# usbDac.net
KiCad netlist of a schematic drawn in EAGLE
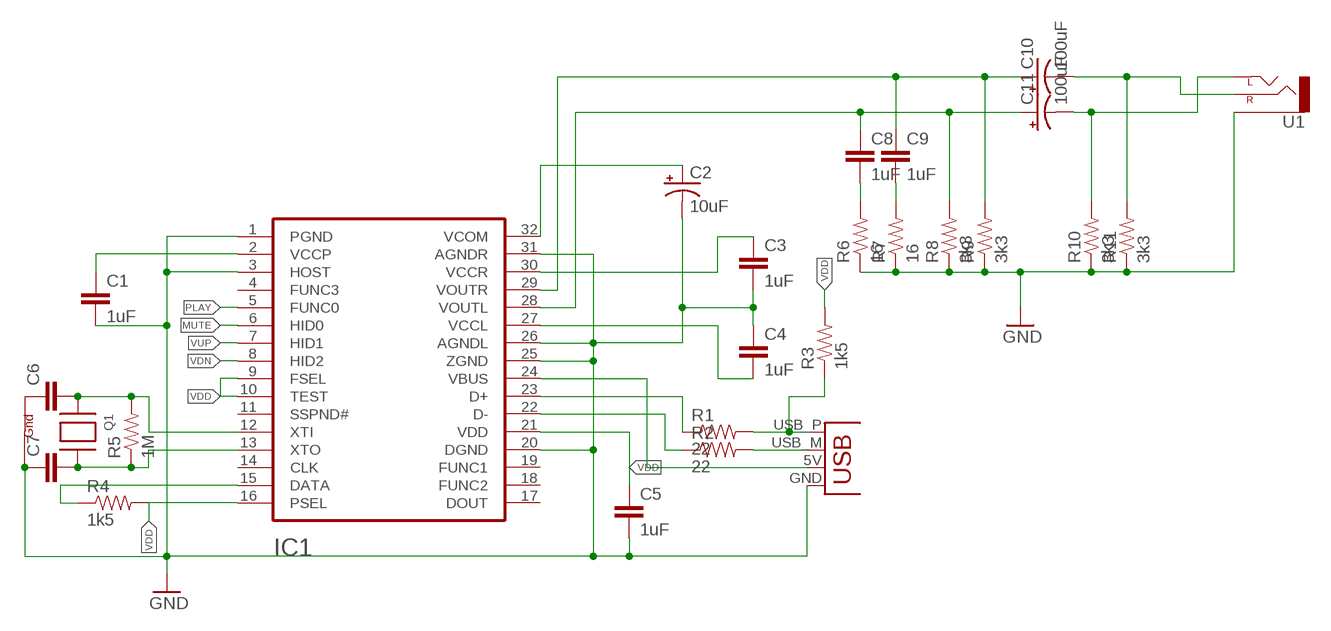
[diagram p0: schematic, sheet 1]

(export (version "E")
  (design (tool "Eeschema 10.0.6"))
  (components
    (comp (ref "C1")
      (value "1uF")
      (footprint "eagle-import:0603-CAP")
      (libsource (lib "eagle-import") (part "CAP0603-CAP"))
    )
    (comp (ref "C2")
      (value "10uF")
      (footprint "eagle-import:EIA3216")
      (libsource (lib "eagle-import") (part "CAP_POL1206"))
    )
    (comp (ref "C3")
      (value "1uF")
      (footprint "eagle-import:0603-CAP")
      (libsource (lib "eagle-import") (part "CAP0603-CAP"))
    )
    (comp (ref "C4")
      (value "1uF")
      (footprint "eagle-import:0603-CAP")
      (libsource (lib "eagle-import") (part "CAP0603-CAP"))
    )
    (comp (ref "C5")
      (value "1uF")
      (footprint "eagle-import:0603-CAP")
      (libsource (lib "eagle-import") (part "CAP0603-CAP"))
    )
    (comp (ref "C6")
      (value "CAP0603-CAP")
      (footprint "eagle-import:0603-CAP")
      (libsource (lib "eagle-import") (part "CAP0603-CAP"))
    )
    (comp (ref "C7")
      (value "CAP0603-CAP")
      (footprint "eagle-import:0603-CAP")
      (libsource (lib "eagle-import") (part "CAP0603-CAP"))
    )
    (comp (ref "C8")
      (value "1uF")
      (footprint "eagle-import:0603-CAP")
      (libsource (lib "eagle-import") (part "CAP0603-CAP"))
    )
    (comp (ref "C9")
      (value "1uF")
      (footprint "eagle-import:0603-CAP")
      (libsource (lib "eagle-import") (part "CAP0603-CAP"))
    )
    (comp (ref "C10")
      (value "100uF")
      (footprint "eagle-import:PANASONIC_C")
      (libsource (lib "eagle-import") (part "CAP_POLC"))
    )
    (comp (ref "C11")
      (value "100uF")
      (footprint "eagle-import:PANASONIC_C")
      (libsource (lib "eagle-import") (part "CAP_POLC"))
    )
    (comp (ref "IC1")
      (value "PCM2706")
      (footprint "eagle-import:TQFP32")
      (libsource (lib "eagle-import") (part "PCM2706"))
    )
    (comp (ref "Q1")
      (value "XTAL-4-3225")
      (footprint "eagle-import:NX3225")
      (libsource (lib "eagle-import") (part "XTAL-4-3225"))
    )
    (comp (ref "R1")
      (value "22")
      (footprint "eagle-import:0603-RES")
      (libsource (lib "eagle-import") (part "RESISTOR0603-RES"))
    )
    (comp (ref "R2")
      (value "22")
      (footprint "eagle-import:0603-RES")
      (libsource (lib "eagle-import") (part "RESISTOR0603-RES"))
    )
    (comp (ref "R3")
      (value "1k5")
      (footprint "eagle-import:0603-RES")
      (libsource (lib "eagle-import") (part "RESISTOR0603-RES"))
    )
    (comp (ref "R4")
      (value "1k5")
      (footprint "eagle-import:0603-RES")
      (libsource (lib "eagle-import") (part "RESISTOR0603-RES"))
    )
    (comp (ref "R5")
      (value "1M")
      (footprint "eagle-import:0603-RES")
      (libsource (lib "eagle-import") (part "RESISTOR0603-RES"))
    )
    (comp (ref "R6")
      (value "16")
      (footprint "eagle-import:0603-RES")
      (libsource (lib "eagle-import") (part "RESISTOR0603-RES"))
    )
    (comp (ref "R7")
      (value "16")
      (footprint "eagle-import:0603-RES")
      (libsource (lib "eagle-import") (part "RESISTOR0603-RES"))
    )
    (comp (ref "R8")
      (value "3k3")
      (footprint "eagle-import:0603-RES")
      (libsource (lib "eagle-import") (part "RESISTOR0603-RES"))
    )
    (comp (ref "R9")
      (value "3k3")
      (footprint "eagle-import:0603-RES")
      (libsource (lib "eagle-import") (part "RESISTOR0603-RES"))
    )
    (comp (ref "R10")
      (value "3k3")
      (footprint "eagle-import:0603-RES")
      (libsource (lib "eagle-import") (part "RESISTOR0603-RES"))
    )
    (comp (ref "R11")
      (value "3k3")
      (footprint "eagle-import:0603-RES")
      (libsource (lib "eagle-import") (part "RESISTOR0603-RES"))
    )
    (comp (ref "U1")
      (value "AUDIO-JACKSMD2")
      (footprint "eagle-import:AUDIO-JACK-3.5MM-SMD")
      (libsource (lib "eagle-import") (part "AUDIO-JACKSMD2"))
    )
    (comp (ref "X1")
      (value "USBPCB")
      (footprint "eagle-import:USB-A-PCB")
      (libsource (lib "eagle-import") (part "USBPCB"))
    )
  )
  (nets
    (net (code "1") (name "GND") (class "Default")
      (node (ref "C1") (pin "2") (pinfunction "2_2") (pintype "passive"))
      (node (ref "C2") (pin "C") (pinfunction "-_C") (pintype "passive"))
      (node (ref "C3") (pin "2") (pinfunction "2_2") (pintype "passive"))
      (node (ref "C4") (pin "1") (pinfunction "1_1") (pintype "passive"))
      (node (ref "C5") (pin "2") (pinfunction "2_2") (pintype "passive"))
      (node (ref "C7") (pin "1") (pinfunction "1_1") (pintype "passive"))
      (node (ref "IC1") (pin "1") (pinfunction "PGND_1") (pintype "bidirectional"))
      (node (ref "IC1") (pin "20") (pinfunction "DGND_20") (pintype "bidirectional"))
      (node (ref "IC1") (pin "25") (pinfunction "ZGND_25") (pintype "bidirectional"))
      (node (ref "IC1") (pin "26") (pinfunction "AGNDL_26") (pintype "bidirectional"))
      (node (ref "IC1") (pin "3") (pinfunction "HOST_3") (pintype "bidirectional"))
      (node (ref "IC1") (pin "31") (pinfunction "AGNDR_31") (pintype "bidirectional"))
      (node (ref "Q1") (pin "2") (pinfunction "G2_2") (pintype "power_in"))
      (node (ref "R10") (pin "1") (pinfunction "1_1") (pintype "passive"))
      (node (ref "R11") (pin "1") (pinfunction "1_1") (pintype "passive"))
      (node (ref "R6") (pin "1") (pinfunction "1_1") (pintype "passive"))
      (node (ref "R7") (pin "1") (pinfunction "1_1") (pintype "passive"))
      (node (ref "R8") (pin "1") (pinfunction "1_1") (pintype "passive"))
      (node (ref "R9") (pin "1") (pinfunction "1_1") (pintype "passive"))
      (node (ref "U1") (pin "SLEEVE") (pinfunction "SLEEVE_SLEEVE") (pintype "bidirectional"))
      (node (ref "X1") (pin "GND") (pinfunction "GND_GND") (pintype "bidirectional"))
    )
    (net (code "2") (name "MUTE") (class "Default")
      (node (ref "IC1") (pin "6") (pinfunction "HID0_6") (pintype "bidirectional"))
    )
    (net (code "3") (name "Net-(C2-+)") (class "Default")
      (node (ref "C2") (pin "A") (pinfunction "+_A") (pintype "passive"))
      (node (ref "IC1") (pin "32") (pinfunction "VCOM_32") (pintype "bidirectional"))
    )
    (net (code "4") (name "Net-(C8-Pad2)") (class "Default")
      (node (ref "C8") (pin "2") (pinfunction "2_2") (pintype "passive"))
      (node (ref "R6") (pin "2") (pinfunction "2_2") (pintype "passive"))
    )
    (net (code "5") (name "Net-(C9-Pad2)") (class "Default")
      (node (ref "C9") (pin "2") (pinfunction "2_2") (pintype "passive"))
      (node (ref "R7") (pin "2") (pinfunction "2_2") (pintype "passive"))
    )
    (net (code "6") (name "Net-(IC1-D+)") (class "Default")
      (node (ref "IC1") (pin "23") (pinfunction "D+_23") (pintype "bidirectional"))
      (node (ref "R1") (pin "1") (pinfunction "1_1") (pintype "passive"))
    )
    (net (code "7") (name "Net-(IC1-D-)") (class "Default")
      (node (ref "IC1") (pin "22") (pinfunction "D-_22") (pintype "bidirectional"))
      (node (ref "R2") (pin "1") (pinfunction "1_1") (pintype "passive"))
    )
    (net (code "8") (name "Net-(IC1-DATA)") (class "Default")
      (node (ref "IC1") (pin "15") (pinfunction "DATA_15") (pintype "bidirectional"))
      (node (ref "R4") (pin "1") (pinfunction "1_1") (pintype "passive"))
    )
    (net (code "9") (name "Net-(IC1-VBUS)") (class "Default")
      (node (ref "IC1") (pin "24") (pinfunction "VBUS_24") (pintype "bidirectional"))
      (node (ref "X1") (pin "5V") (pinfunction "VBUS_5V") (pintype "bidirectional"))
    )
    (net (code "10") (name "Net-(IC1-VCCL)") (class "Default")
      (node (ref "C4") (pin "2") (pinfunction "2_2") (pintype "passive"))
      (node (ref "IC1") (pin "27") (pinfunction "VCCL_27") (pintype "bidirectional"))
    )
    (net (code "11") (name "Net-(IC1-VCCP)") (class "Default")
      (node (ref "C1") (pin "1") (pinfunction "1_1") (pintype "passive"))
      (node (ref "IC1") (pin "2") (pinfunction "VCCP_2") (pintype "bidirectional"))
    )
    (net (code "12") (name "Net-(IC1-VCCR)") (class "Default")
      (node (ref "C3") (pin "1") (pinfunction "1_1") (pintype "passive"))
      (node (ref "IC1") (pin "30") (pinfunction "VCCR_30") (pintype "bidirectional"))
    )
    (net (code "13") (name "Net-(IC1-VOUTL)") (class "Default")
      (node (ref "C11") (pin "+") (pinfunction "+_+") (pintype "passive"))
      (node (ref "C8") (pin "1") (pinfunction "1_1") (pintype "passive"))
      (node (ref "IC1") (pin "28") (pinfunction "VOUTL_28") (pintype "bidirectional"))
      (node (ref "R8") (pin "2") (pinfunction "2_2") (pintype "passive"))
    )
    (net (code "14") (name "Net-(IC1-VOUTR)") (class "Default")
      (node (ref "C10") (pin "+") (pinfunction "+_+") (pintype "passive"))
      (node (ref "C9") (pin "1") (pinfunction "1_1") (pintype "passive"))
      (node (ref "IC1") (pin "29") (pinfunction "VOUTR_29") (pintype "bidirectional"))
      (node (ref "R9") (pin "2") (pinfunction "2_2") (pintype "passive"))
    )
    (net (code "15") (name "Net-(IC1-XTI)") (class "Default")
      (node (ref "C6") (pin "2") (pinfunction "2_2") (pintype "passive"))
      (node (ref "IC1") (pin "12") (pinfunction "XTI_12") (pintype "bidirectional"))
      (node (ref "Q1") (pin "1") (pinfunction "X1_1") (pintype "bidirectional"))
      (node (ref "R5") (pin "2") (pinfunction "2_2") (pintype "passive"))
    )
    (net (code "16") (name "Net-(IC1-XTO)") (class "Default")
      (node (ref "C7") (pin "2") (pinfunction "2_2") (pintype "passive"))
      (node (ref "IC1") (pin "13") (pinfunction "XTO_13") (pintype "bidirectional"))
      (node (ref "Q1") (pin "3") (pinfunction "X2_3") (pintype "bidirectional"))
      (node (ref "R5") (pin "1") (pinfunction "1_1") (pintype "passive"))
    )
    (net (code "17") (name "Net-(Q1-G1)") (class "Default")
      (node (ref "C6") (pin "1") (pinfunction "1_1") (pintype "passive"))
      (node (ref "Q1") (pin "4") (pinfunction "G1_4") (pintype "power_in"))
    )
    (net (code "18") (name "Net-(U1-LEFT)") (class "Default")
      (node (ref "C11") (pin "-") (pinfunction "-_-") (pintype "passive"))
      (node (ref "R10") (pin "2") (pinfunction "2_2") (pintype "passive"))
      (node (ref "U1") (pin "TIP") (pinfunction "LEFT_TIP") (pintype "bidirectional"))
    )
    (net (code "19") (name "Net-(U1-RIGHT)") (class "Default")
      (node (ref "C10") (pin "-") (pinfunction "-_-") (pintype "passive"))
      (node (ref "R11") (pin "2") (pinfunction "2_2") (pintype "passive"))
      (node (ref "U1") (pin "RING") (pinfunction "RIGHT_RING") (pintype "bidirectional"))
    )
    (net (code "20") (name "Net-(X1-D+)") (class "Default")
      (node (ref "R1") (pin "2") (pinfunction "2_2") (pintype "passive"))
      (node (ref "R3") (pin "1") (pinfunction "1_1") (pintype "passive"))
      (node (ref "X1") (pin "USB_P") (pinfunction "D+_USB_P") (pintype "bidirectional"))
    )
    (net (code "21") (name "Net-(X1-D-)") (class "Default")
      (node (ref "R2") (pin "2") (pinfunction "2_2") (pintype "passive"))
      (node (ref "X1") (pin "USB_M") (pinfunction "D-_USB_M") (pintype "bidirectional"))
    )
    (net (code "22") (name "PLAY") (class "Default")
      (node (ref "IC1") (pin "5") (pinfunction "FUNC0_5") (pintype "bidirectional"))
    )
    (net (code "23") (name "VDD") (class "Default")
      (node (ref "C5") (pin "1") (pinfunction "1_1") (pintype "passive"))
      (node (ref "IC1") (pin "10") (pinfunction "TEST_10") (pintype "bidirectional"))
      (node (ref "IC1") (pin "16") (pinfunction "PSEL_16") (pintype "bidirectional"))
      (node (ref "IC1") (pin "21") (pinfunction "VDD_21") (pintype "bidirectional"))
      (node (ref "IC1") (pin "9") (pinfunction "FSEL_9") (pintype "bidirectional"))
      (node (ref "R3") (pin "2") (pinfunction "2_2") (pintype "passive"))
      (node (ref "R4") (pin "2") (pinfunction "2_2") (pintype "passive"))
    )
    (net (code "24") (name "VDN") (class "Default")
      (node (ref "IC1") (pin "8") (pinfunction "HID2_8") (pintype "bidirectional"))
    )
    (net (code "25") (name "VUP") (class "Default")
      (node (ref "IC1") (pin "7") (pinfunction "HID1_7") (pintype "bidirectional"))
    )
    (net (code "26") (name "unconnected-(IC1-CLK-Pad14)") (class "Default")
      (node (ref "IC1") (pin "14") (pinfunction "CLK_14") (pintype "bidirectional"))
    )
    (net (code "27") (name "unconnected-(IC1-DOUT-Pad17)") (class "Default")
      (node (ref "IC1") (pin "17") (pinfunction "DOUT_17") (pintype "bidirectional"))
    )
    (net (code "28") (name "unconnected-(IC1-FUNC1-Pad19)") (class "Default")
      (node (ref "IC1") (pin "19") (pinfunction "FUNC1_19") (pintype "bidirectional"))
    )
    (net (code "29") (name "unconnected-(IC1-FUNC2-Pad18)") (class "Default")
      (node (ref "IC1") (pin "18") (pinfunction "FUNC2_18") (pintype "bidirectional"))
    )
    (net (code "30") (name "unconnected-(IC1-FUNC3-Pad4)") (class "Default")
      (node (ref "IC1") (pin "4") (pinfunction "FUNC3_4") (pintype "bidirectional"))
    )
    (net (code "31") (name "unconnected-(IC1-SSPND#-Pad11)") (class "Default")
      (node (ref "IC1") (pin "11") (pinfunction "SSPND#_11") (pintype "bidirectional"))
    )
  )
)
